# TDA2003-Amplifier-Stereo-x.net
KiCad netlist of a schematic drawn in EAGLE
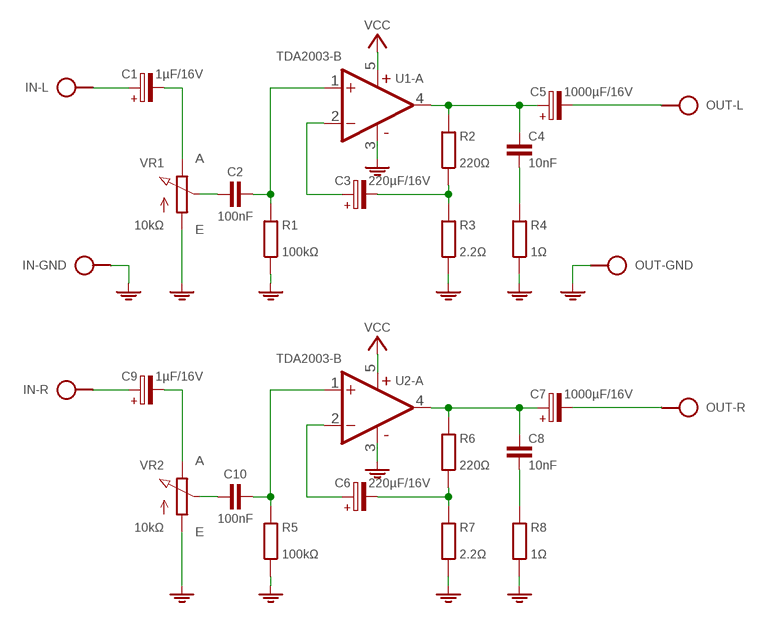
[diagram p0: schematic, sheet 1]

(export (version "E")
  (design (tool "Eeschema 10.0.6"))
  (components
    (comp (ref "C1")
      (value "1µF/16V")
      (footprint "eagle-import:E2,5-4")
      (libsource (lib "eagle-import") (part "CPOL-HE2,5-4"))
    )
    (comp (ref "C2")
      (value "100nF")
      (footprint "eagle-import:C050-020X044_V")
      (libsource (lib "eagle-import") (part "C-H050-020X044/V"))
    )
    (comp (ref "C3")
      (value "220µF/16V")
      (footprint "eagle-import:E5-5")
      (libsource (lib "eagle-import") (part "CPOL-HE5-5"))
    )
    (comp (ref "C4")
      (value "10nF")
      (footprint "eagle-import:C050-025X075_V")
      (libsource (lib "eagle-import") (part "C050-025X075/V"))
    )
    (comp (ref "C5")
      (value "1000µF/16V")
      (footprint "eagle-import:E5-5")
      (libsource (lib "eagle-import") (part "CPOL-HE5-5"))
    )
    (comp (ref "C6")
      (value "220µF/16V")
      (footprint "eagle-import:E5-5")
      (libsource (lib "eagle-import") (part "CPOL-HE5-5"))
    )
    (comp (ref "C7")
      (value "1000µF/16V")
      (footprint "eagle-import:E5-5")
      (libsource (lib "eagle-import") (part "CPOL-HE5-5"))
    )
    (comp (ref "C8")
      (value "10nF")
      (footprint "eagle-import:C050-025X075_V")
      (libsource (lib "eagle-import") (part "C050-025X075/V"))
    )
    (comp (ref "C9")
      (value "1µF/16V")
      (footprint "eagle-import:E2,5-4")
      (libsource (lib "eagle-import") (part "CPOL-HE2,5-4"))
    )
    (comp (ref "C10")
      (value "100nF")
      (footprint "eagle-import:C050-020X044_V")
      (libsource (lib "eagle-import") (part "C-H050-020X044/V"))
    )
    (comp (ref "IN")
      (value "SAUDIO")
      (footprint "eagle-import:SPAD-3")
      (libsource (lib "eagle-import") (part "SAUDIO"))
    )
    (comp (ref "OUT")
      (value "SAUDIO")
      (footprint "eagle-import:SPAD-3")
      (libsource (lib "eagle-import") (part "SAUDIO"))
    )
    (comp (ref "PWR")
      (value "VCC_GNDL")
      (footprint "eagle-import:SPAD-+")
      (libsource (lib "eagle-import") (part "VCC_GNDL"))
    )
    (comp (ref "R1")
      (value "100kΩ")
      (footprint "eagle-import:0204_10-V")
      (libsource (lib "eagle-import") (part "R0204/10-V"))
    )
    (comp (ref "R2")
      (value "220Ω")
      (footprint "eagle-import:0204_10-V")
      (libsource (lib "eagle-import") (part "R0204/10-V"))
    )
    (comp (ref "R3")
      (value "2.2Ω")
      (footprint "eagle-import:0204_10-V")
      (libsource (lib "eagle-import") (part "R0204/10-V"))
    )
    (comp (ref "R4")
      (value "1Ω")
      (footprint "eagle-import:0204_10-V")
      (libsource (lib "eagle-import") (part "R0204/10-V"))
    )
    (comp (ref "R5")
      (value "100kΩ")
      (footprint "eagle-import:0204_10-V")
      (libsource (lib "eagle-import") (part "R0204/10-V"))
    )
    (comp (ref "R6")
      (value "220Ω")
      (footprint "eagle-import:0204_10-V")
      (libsource (lib "eagle-import") (part "R0204/10-V"))
    )
    (comp (ref "R7")
      (value "2.2Ω")
      (footprint "eagle-import:0204_10-V")
      (libsource (lib "eagle-import") (part "R0204/10-V"))
    )
    (comp (ref "R8")
      (value "1Ω")
      (footprint "eagle-import:0204_10-V")
      (libsource (lib "eagle-import") (part "R0204/10-V"))
    )
    (comp (ref "U1")
      (value "TDA2003-B")
      (footprint "eagle-import:TO220-B5")
      (libsource (lib "eagle-import") (part "TDA2003-B"))
    )
    (comp (ref "U2")
      (value "TDA2003-B")
      (footprint "eagle-import:TO220-B5")
      (libsource (lib "eagle-import") (part "TDA2003-B"))
    )
    (comp (ref "VR1")
      (value "10kΩ")
      (footprint "eagle-import:CONN-3P")
      (libsource (lib "eagle-import") (part "POT-3P"))
    )
    (comp (ref "VR2")
      (value "10kΩ")
      (footprint "eagle-import:CONN-3P")
      (libsource (lib "eagle-import") (part "POT-3P"))
    )
  )
  (nets
    (net (code "1") (name "GND") (class "Default")
      (node (ref "IN") (pin "2") (pinfunction "P$1_2") (pintype "passive"))
      (node (ref "OUT") (pin "2") (pinfunction "P$1_2") (pintype "passive"))
      (node (ref "PWR") (pin "1") (pinfunction "GND_1") (pintype "power_in"))
      (node (ref "R1") (pin "2") (pinfunction "1_2") (pintype "passive"))
      (node (ref "R3") (pin "2") (pinfunction "1_2") (pintype "passive"))
      (node (ref "R4") (pin "2") (pinfunction "1_2") (pintype "passive"))
      (node (ref "R5") (pin "2") (pinfunction "1_2") (pintype "passive"))
      (node (ref "R7") (pin "2") (pinfunction "1_2") (pintype "passive"))
      (node (ref "R8") (pin "2") (pinfunction "1_2") (pintype "passive"))
      (node (ref "U1") (pin "3") (pinfunction "V-_3") (pintype "power_in"))
      (node (ref "U2") (pin "3") (pinfunction "V-_3") (pintype "power_in"))
      (node (ref "VR1") (pin "1") (pinfunction "A_1") (pintype "passive"))
      (node (ref "VR2") (pin "1") (pinfunction "A_1") (pintype "passive"))
    )
    (net (code "2") (name "Net-(INB-P$1)") (class "Default")
      (node (ref "C1") (pin "+") (pinfunction "+_+") (pintype "passive"))
      (node (ref "IN") (pin "1") (pinfunction "P$1_1") (pintype "passive"))
    )
    (net (code "3") (name "Net-(INC-P$1)") (class "Default")
      (node (ref "C9") (pin "+") (pinfunction "+_+") (pintype "passive"))
      (node (ref "IN") (pin "3") (pinfunction "P$1_3") (pintype "passive"))
    )
    (net (code "4") (name "Net-(OUTB-P$1)") (class "Default")
      (node (ref "C5") (pin "-") (pinfunction "-_-") (pintype "passive"))
      (node (ref "OUT") (pin "1") (pinfunction "P$1_1") (pintype "passive"))
    )
    (net (code "5") (name "Net-(OUTC-P$1)") (class "Default")
      (node (ref "C7") (pin "-") (pinfunction "-_-") (pintype "passive"))
      (node (ref "OUT") (pin "3") (pinfunction "P$1_3") (pintype "passive"))
    )
    (net (code "6") (name "Net-(R1-2)") (class "Default")
      (node (ref "C2") (pin "2") (pinfunction "2_2") (pintype "passive"))
      (node (ref "R1") (pin "1") (pinfunction "2_1") (pintype "passive"))
      (node (ref "U1") (pin "1") (pinfunction "+IN_1") (pintype "input"))
    )
    (net (code "7") (name "Net-(R2-1)") (class "Default")
      (node (ref "C3") (pin "-") (pinfunction "-_-") (pintype "passive"))
      (node (ref "R2") (pin "2") (pinfunction "1_2") (pintype "passive"))
      (node (ref "R3") (pin "1") (pinfunction "2_1") (pintype "passive"))
    )
    (net (code "8") (name "Net-(R2-2)") (class "Default")
      (node (ref "C4") (pin "1") (pinfunction "1_1") (pintype "passive"))
      (node (ref "C5") (pin "+") (pinfunction "+_+") (pintype "passive"))
      (node (ref "R2") (pin "1") (pinfunction "2_1") (pintype "passive"))
      (node (ref "U1") (pin "4") (pinfunction "OUT_4") (pintype "output"))
    )
    (net (code "9") (name "Net-(R4-2)") (class "Default")
      (node (ref "C4") (pin "2") (pinfunction "2_2") (pintype "passive"))
      (node (ref "R4") (pin "1") (pinfunction "2_1") (pintype "passive"))
    )
    (net (code "10") (name "Net-(R5-2)") (class "Default")
      (node (ref "C10") (pin "2") (pinfunction "2_2") (pintype "passive"))
      (node (ref "R5") (pin "1") (pinfunction "2_1") (pintype "passive"))
      (node (ref "U2") (pin "1") (pinfunction "+IN_1") (pintype "input"))
    )
    (net (code "11") (name "Net-(R6-1)") (class "Default")
      (node (ref "C6") (pin "-") (pinfunction "-_-") (pintype "passive"))
      (node (ref "R6") (pin "2") (pinfunction "1_2") (pintype "passive"))
      (node (ref "R7") (pin "1") (pinfunction "2_1") (pintype "passive"))
    )
    (net (code "12") (name "Net-(R6-2)") (class "Default")
      (node (ref "C7") (pin "+") (pinfunction "+_+") (pintype "passive"))
      (node (ref "C8") (pin "1") (pinfunction "1_1") (pintype "passive"))
      (node (ref "R6") (pin "1") (pinfunction "2_1") (pintype "passive"))
      (node (ref "U2") (pin "4") (pinfunction "OUT_4") (pintype "output"))
    )
    (net (code "13") (name "Net-(R8-2)") (class "Default")
      (node (ref "C8") (pin "2") (pinfunction "2_2") (pintype "passive"))
      (node (ref "R8") (pin "1") (pinfunction "2_1") (pintype "passive"))
    )
    (net (code "14") (name "Net-(U1A--IN)") (class "Default")
      (node (ref "C3") (pin "+") (pinfunction "+_+") (pintype "passive"))
      (node (ref "U1") (pin "2") (pinfunction "-IN_2") (pintype "input"))
    )
    (net (code "15") (name "Net-(U2A--IN)") (class "Default")
      (node (ref "C6") (pin "+") (pinfunction "+_+") (pintype "passive"))
      (node (ref "U2") (pin "2") (pinfunction "-IN_2") (pintype "input"))
    )
    (net (code "16") (name "Net-(VR1-E)") (class "Default")
      (node (ref "C1") (pin "-") (pinfunction "-_-") (pintype "passive"))
      (node (ref "VR1") (pin "3") (pinfunction "E_3") (pintype "passive"))
    )
    (net (code "17") (name "Net-(VR1-S)") (class "Default")
      (node (ref "C2") (pin "1") (pinfunction "1_1") (pintype "passive"))
      (node (ref "VR1") (pin "2") (pinfunction "S_2") (pintype "passive"))
    )
    (net (code "18") (name "Net-(VR2-E)") (class "Default")
      (node (ref "C9") (pin "-") (pinfunction "-_-") (pintype "passive"))
      (node (ref "VR2") (pin "3") (pinfunction "E_3") (pintype "passive"))
    )
    (net (code "19") (name "Net-(VR2-S)") (class "Default")
      (node (ref "C10") (pin "1") (pinfunction "1_1") (pintype "passive"))
      (node (ref "VR2") (pin "2") (pinfunction "S_2") (pintype "passive"))
    )
    (net (code "20") (name "VCC") (class "Default")
      (node (ref "PWR") (pin "2") (pinfunction "VCC_2") (pintype "power_in"))
      (node (ref "U1") (pin "5") (pinfunction "V+_5") (pintype "power_in"))
      (node (ref "U2") (pin "5") (pinfunction "V+_5") (pintype "power_in"))
    )
  )
)
